# slush_cap_board_rev_b.net
KiCad netlist of a schematic drawn in EAGLE
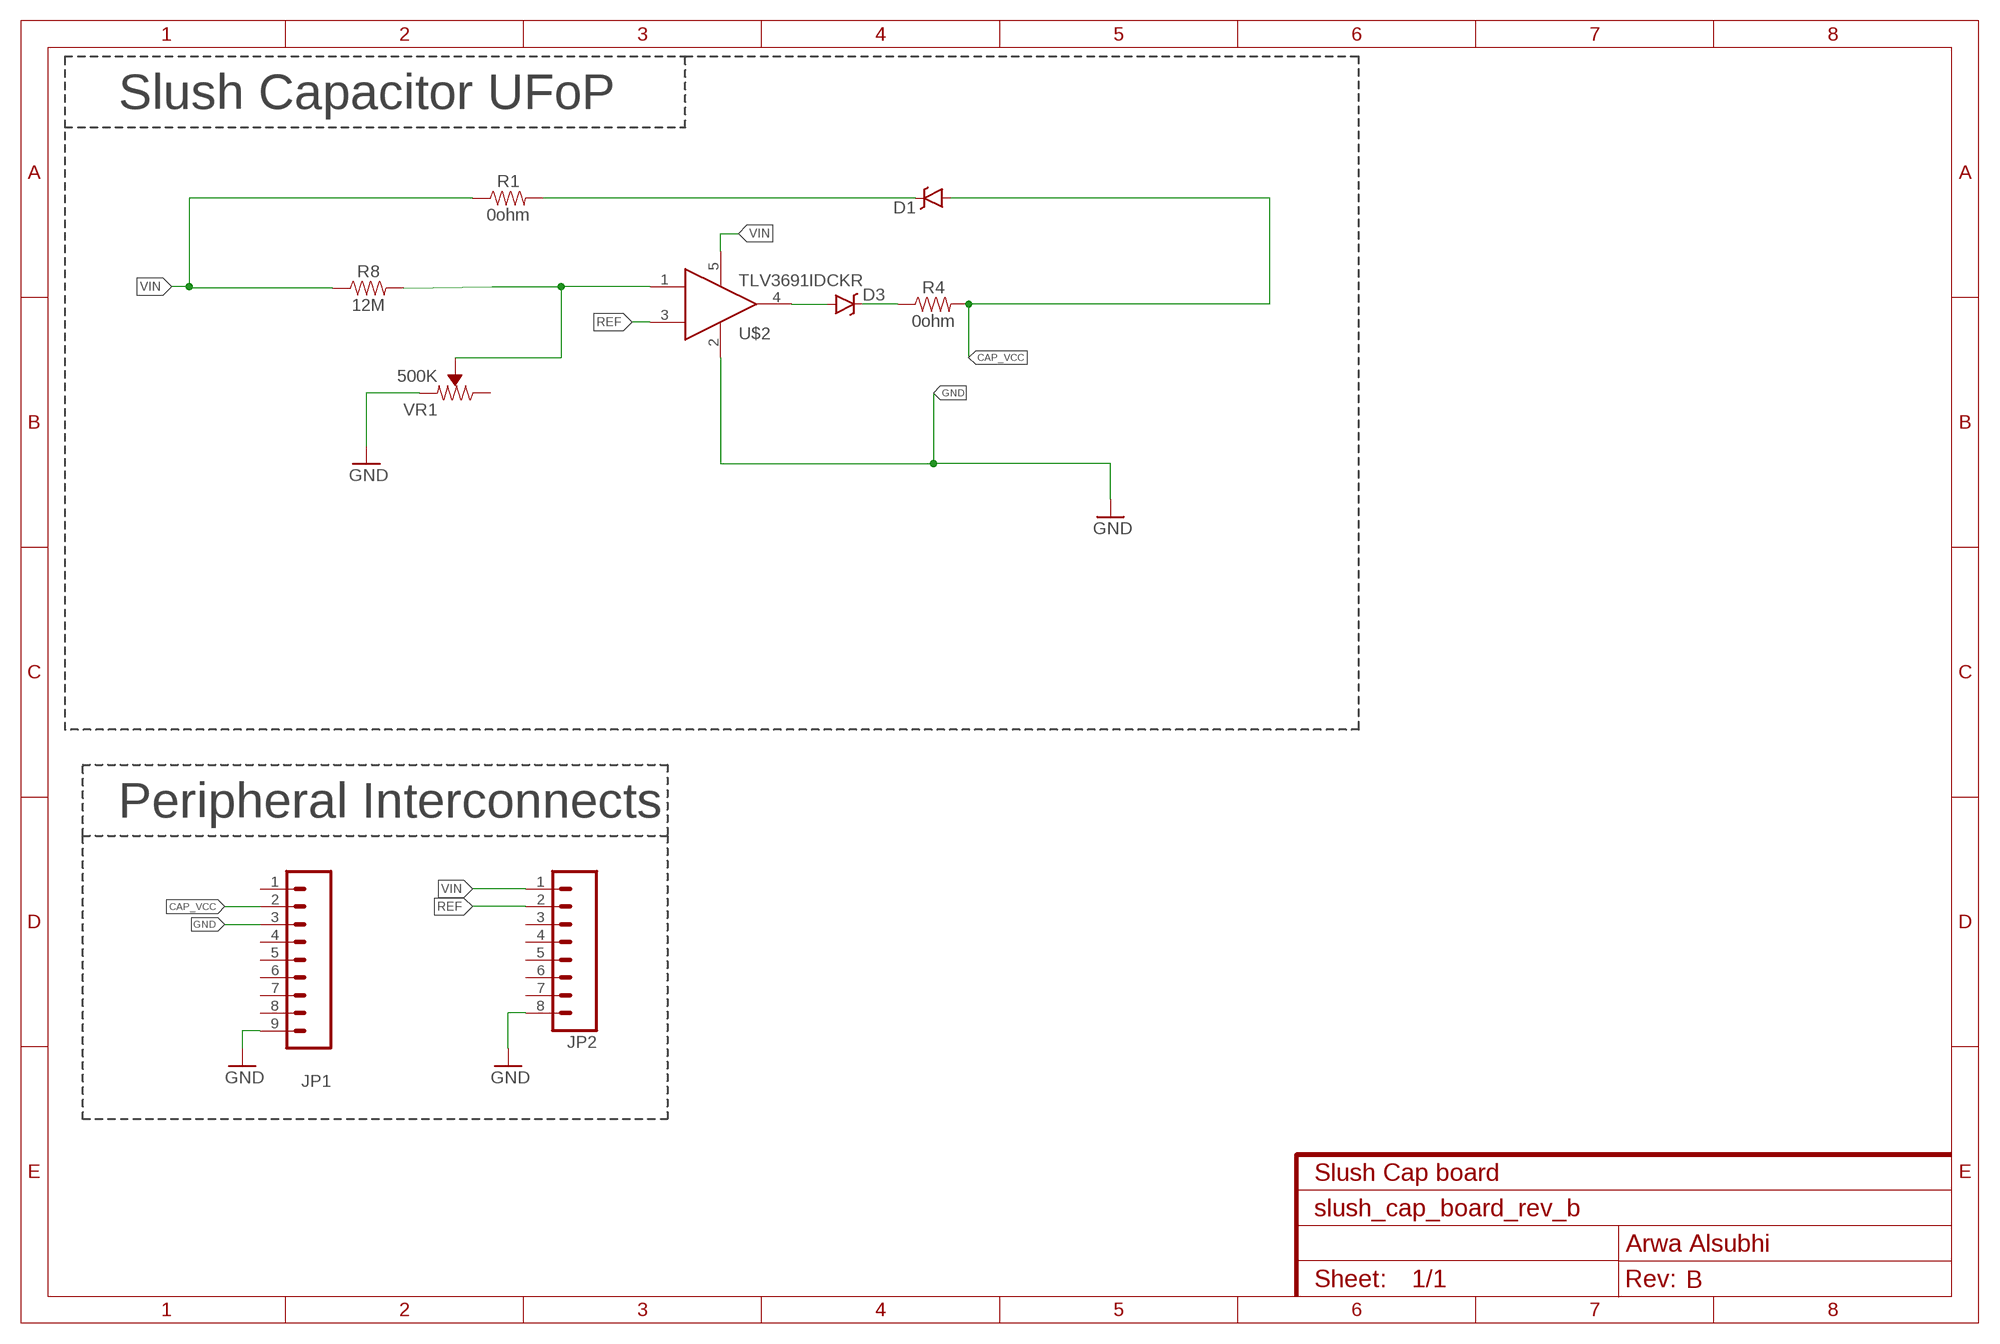
[diagram p0: schematic, sheet 1]

(export (version "E")
  (design (tool "Eeschema 10.0.6"))
  (components
    (comp (ref "D1")
      (value "RB751")
      (footprint "eagle-import:SOD-523")
      (fields (field (name "MPN") "BAS40-02V-V-G-08"))
      (libsource (lib "eagle-import") (part "DIODE-SCHOTTKY-RB751"))
    )
    (comp (ref "D3")
      (value "RB751")
      (footprint "eagle-import:SOD-523")
      (fields (field (name "MPN") "BAS40-02V-V-G-08"))
      (libsource (lib "eagle-import") (part "DIODE-SCHOTTKY-RB751"))
    )
    (comp (ref "JP1")
      (value "M091.27MM")
      (footprint "eagle-import:1X09-1.27MM")
      (fields (field (name "MANUFACTURERPARTNUMBER") "GRPB091VWVN-RC ") (field (name "MPN") "GRPB091VWVN-RC"))
      (libsource (lib "eagle-import") (part "M091.27MM"))
    )
    (comp (ref "JP2")
      (value "M081.27MM")
      (footprint "eagle-import:1X08-1.27MM")
      (fields (field (name "MANUFACTURERPARTNUMBER") "GRPB081VWVN-RC "))
      (libsource (lib "eagle-import") (part "M081.27MM"))
    )
    (comp (ref "R1")
      (value "0ohm")
      (footprint "eagle-import:0603")
      (libsource (lib "eagle-import") (part "0603-RESISTOR-0603-1/10W-1%"))
    )
    (comp (ref "R4")
      (value "0ohm")
      (footprint "eagle-import:0603")
      (libsource (lib "eagle-import") (part "0603-RESISTOR-0603-1/10W-1%"))
    )
    (comp (ref "R8")
      (value "12M")
      (footprint "eagle-import:0805")
      (libsource (lib "eagle-import") (part "0.3OHM-0805-1/8W-1%"))
    )
    (comp (ref "U$2")
      (value "TLV3691IDCKR")
      (footprint "eagle-import:SOT353")
      (libsource (lib "eagle-import") (part "TLV3691IDCKR"))
    )
    (comp (ref "VR1")
      (value "500K")
      (footprint "eagle-import:TRIMPOT-SMD-3MM-CLOSED")
      (libsource (lib "eagle-import") (part "TRIMPOT-SMD-3MM-CLOSED-1/8W-20%"))
    )
  )
  (nets
    (net (code "1") (name "CAP_VCC") (class "Default")
      (node (ref "D1") (pin "A") (pinfunction "A_A") (pintype "passive"))
      (node (ref "JP1") (pin "2") (pinfunction "2_2") (pintype "passive"))
      (node (ref "R4") (pin "2") (pinfunction "2_2") (pintype "passive"))
    )
    (net (code "2") (name "GND") (class "Default")
      (node (ref "JP1") (pin "3") (pinfunction "3_3") (pintype "passive"))
      (node (ref "JP1") (pin "9") (pinfunction "9_9") (pintype "passive"))
      (node (ref "JP2") (pin "8") (pinfunction "8_8") (pintype "passive"))
      (node (ref "U$2") (pin "2") (pinfunction "2_2") (pintype "bidirectional"))
      (node (ref "VR1") (pin "1") (pinfunction "CCW_1") (pintype "passive"))
    )
    (net (code "3") (name "Net-(D1-PadC)") (class "Default")
      (node (ref "D1") (pin "C") (pinfunction "C_C") (pintype "passive"))
      (node (ref "R1") (pin "2") (pinfunction "2_2") (pintype "passive"))
    )
    (net (code "4") (name "Net-(D3-PadA)") (class "Default")
      (node (ref "D3") (pin "A") (pinfunction "A_A") (pintype "passive"))
      (node (ref "U$2") (pin "4") (pinfunction "4_4") (pintype "bidirectional"))
    )
    (net (code "5") (name "Net-(D3-PadC)") (class "Default")
      (node (ref "D3") (pin "C") (pinfunction "C_C") (pintype "passive"))
      (node (ref "R4") (pin "1") (pinfunction "1_1") (pintype "passive"))
    )
    (net (code "6") (name "Net-(VR1-WIPER)") (class "Default")
      (node (ref "R8") (pin "2") (pinfunction "2_2") (pintype "passive"))
      (node (ref "U$2") (pin "1") (pinfunction "1_1") (pintype "bidirectional"))
      (node (ref "VR1") (pin "2") (pinfunction "WIPER_2") (pintype "passive"))
    )
    (net (code "7") (name "REF") (class "Default")
      (node (ref "JP2") (pin "2") (pinfunction "2_2") (pintype "passive"))
      (node (ref "U$2") (pin "3") (pinfunction "3_3") (pintype "bidirectional"))
    )
    (net (code "8") (name "VIN") (class "Default")
      (node (ref "JP2") (pin "1") (pinfunction "1_1") (pintype "passive"))
      (node (ref "R1") (pin "1") (pinfunction "1_1") (pintype "passive"))
      (node (ref "R8") (pin "1") (pinfunction "1_1") (pintype "passive"))
      (node (ref "U$2") (pin "5") (pinfunction "5_5") (pintype "bidirectional"))
    )
    (net (code "9") (name "unconnected-(JP1-Pad1)") (class "Default")
      (node (ref "JP1") (pin "1") (pinfunction "1_1") (pintype "passive"))
    )
    (net (code "10") (name "unconnected-(JP1-Pad4)") (class "Default")
      (node (ref "JP1") (pin "4") (pinfunction "4_4") (pintype "passive"))
    )
    (net (code "11") (name "unconnected-(JP1-Pad5)") (class "Default")
      (node (ref "JP1") (pin "5") (pinfunction "5_5") (pintype "passive"))
    )
    (net (code "12") (name "unconnected-(JP1-Pad6)") (class "Default")
      (node (ref "JP1") (pin "6") (pinfunction "6_6") (pintype "passive"))
    )
    (net (code "13") (name "unconnected-(JP1-Pad7)") (class "Default")
      (node (ref "JP1") (pin "7") (pinfunction "7_7") (pintype "passive"))
    )
    (net (code "14") (name "unconnected-(JP1-Pad8)") (class "Default")
      (node (ref "JP1") (pin "8") (pinfunction "8_8") (pintype "passive"))
    )
    (net (code "15") (name "unconnected-(JP2-Pad3)") (class "Default")
      (node (ref "JP2") (pin "3") (pinfunction "3_3") (pintype "passive"))
    )
    (net (code "16") (name "unconnected-(JP2-Pad4)") (class "Default")
      (node (ref "JP2") (pin "4") (pinfunction "4_4") (pintype "passive"))
    )
    (net (code "17") (name "unconnected-(JP2-Pad5)") (class "Default")
      (node (ref "JP2") (pin "5") (pinfunction "5_5") (pintype "passive"))
    )
    (net (code "18") (name "unconnected-(JP2-Pad6)") (class "Default")
      (node (ref "JP2") (pin "6") (pinfunction "6_6") (pintype "passive"))
    )
    (net (code "19") (name "unconnected-(JP2-Pad7)") (class "Default")
      (node (ref "JP2") (pin "7") (pinfunction "7_7") (pintype "passive"))
    )
    (net (code "20") (name "unconnected-(VR1-CW-Pad3)") (class "Default")
      (node (ref "VR1") (pin "3") (pinfunction "CW_3") (pintype "passive"))
    )
  )
)
